# laser_zender.net
KiCad netlist of a schematic drawn in EAGLE
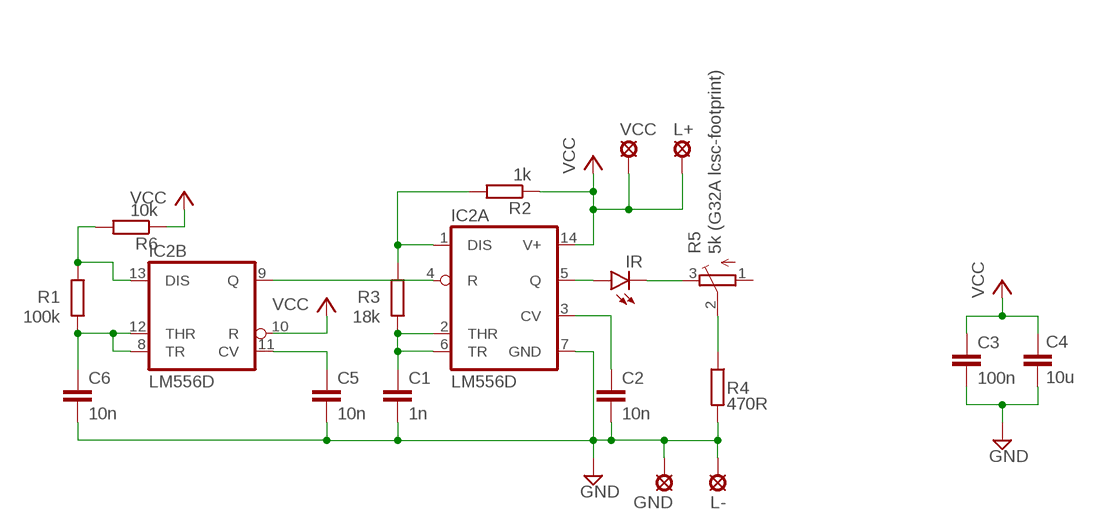
[diagram p0: schematic, sheet 1]

(export (version "E")
  (design (tool "Eeschema 10.0.6"))
  (components
    (comp (ref "C1")
      (value "1n")
      (footprint "eagle-import:C0805")
      (libsource (lib "eagle-import") (part "C-EUC0805"))
    )
    (comp (ref "C2")
      (value "10n")
      (footprint "eagle-import:C0805")
      (libsource (lib "eagle-import") (part "C-EUC0805"))
    )
    (comp (ref "C3")
      (value "100n")
      (footprint "eagle-import:C0805")
      (libsource (lib "eagle-import") (part "C-EUC0805"))
    )
    (comp (ref "C4")
      (value "10u")
      (footprint "eagle-import:C0805")
      (libsource (lib "eagle-import") (part "C-EUC0805"))
    )
    (comp (ref "C5")
      (value "10n")
      (footprint "eagle-import:C0805")
      (libsource (lib "eagle-import") (part "C-EUC0805"))
    )
    (comp (ref "C6")
      (value "10n")
      (footprint "eagle-import:C0805")
      (libsource (lib "eagle-import") (part "C-EUC0805"))
    )
    (comp (ref "GND")
      (value "LSP10")
      (footprint "eagle-import:LSP10")
      (libsource (lib "eagle-import") (part "LSP10"))
    )
    (comp (ref "IC2")
      (value "LM556D")
      (footprint "eagle-import:SO14")
      (libsource (lib "eagle-import") (part "556DLM"))
    )
    (comp (ref "IR")
      (value "LEDCHIPLED_0805")
      (footprint "eagle-import:CHIPLED_0805")
      (libsource (lib "eagle-import") (part "LEDCHIPLED_0805"))
    )
    (comp (ref "L+")
      (value "LSP10")
      (footprint "eagle-import:LSP10")
      (libsource (lib "eagle-import") (part "LSP10"))
    )
    (comp (ref "L-")
      (value "LSP10")
      (footprint "eagle-import:LSP10")
      (libsource (lib "eagle-import") (part "LSP10"))
    )
    (comp (ref "R1")
      (value "100k")
      (footprint "eagle-import:R0805")
      (libsource (lib "eagle-import") (part "R-EU_R0805"))
    )
    (comp (ref "R2")
      (value "1k")
      (footprint "eagle-import:R0805")
      (libsource (lib "eagle-import") (part "R-EU_R0805"))
    )
    (comp (ref "R3")
      (value "18k")
      (footprint "eagle-import:R0805")
      (libsource (lib "eagle-import") (part "R-EU_R0805"))
    )
    (comp (ref "R4")
      (value "470R")
      (footprint "eagle-import:R0805")
      (libsource (lib "eagle-import") (part "R-EU_R0805"))
    )
    (comp (ref "R5")
      (value "5k (G32A lcsc-footprint)")
      (footprint "eagle-import:3223W")
      (libsource (lib "eagle-import") (part "TRIM_EU-3223W"))
    )
    (comp (ref "R6")
      (value "10k")
      (footprint "eagle-import:R0805")
      (libsource (lib "eagle-import") (part "R-EU_R0805"))
    )
    (comp (ref "VCC")
      (value "LSP10")
      (footprint "eagle-import:LSP10")
      (libsource (lib "eagle-import") (part "LSP10"))
    )
  )
  (nets
    (net (code "1") (name "GND") (class "Default")
      (node (ref "C1") (pin "2") (pinfunction "2_2") (pintype "passive"))
      (node (ref "C2") (pin "2") (pinfunction "2_2") (pintype "passive"))
      (node (ref "C3") (pin "2") (pinfunction "2_2") (pintype "passive"))
      (node (ref "C4") (pin "2") (pinfunction "2_2") (pintype "passive"))
      (node (ref "C5") (pin "2") (pinfunction "2_2") (pintype "passive"))
      (node (ref "C6") (pin "2") (pinfunction "2_2") (pintype "passive"))
      (node (ref "GND") (pin "MP") (pinfunction "MP_MP") (pintype "passive"))
      (node (ref "IC2") (pin "7") (pinfunction "GND_7") (pintype "power_in"))
      (node (ref "L-") (pin "MP") (pinfunction "MP_MP") (pintype "passive"))
      (node (ref "R4") (pin "2") (pinfunction "2_2") (pintype "passive"))
    )
    (net (code "2") (name "Net-(IC2A-CV)") (class "Default")
      (node (ref "C2") (pin "1") (pinfunction "1_1") (pintype "passive"))
      (node (ref "IC2") (pin "3") (pinfunction "CV_3") (pintype "input"))
    )
    (net (code "3") (name "Net-(IC2A-DIS)") (class "Default")
      (node (ref "IC2") (pin "1") (pinfunction "DIS_1") (pintype "input"))
      (node (ref "R2") (pin "2") (pinfunction "2_2") (pintype "passive"))
      (node (ref "R3") (pin "2") (pinfunction "2_2") (pintype "passive"))
    )
    (net (code "4") (name "Net-(IC2A-Q)") (class "Default")
      (node (ref "IC2") (pin "5") (pinfunction "Q_5") (pintype "output"))
      (node (ref "IR") (pin "A") (pinfunction "A_A") (pintype "passive"))
    )
    (net (code "5") (name "Net-(IC2A-R)") (class "Default")
      (node (ref "IC2") (pin "4") (pinfunction "R_4") (pintype "input"))
      (node (ref "IC2") (pin "9") (pinfunction "Q_9") (pintype "output"))
    )
    (net (code "6") (name "Net-(IC2A-THR)") (class "Default")
      (node (ref "C1") (pin "1") (pinfunction "1_1") (pintype "passive"))
      (node (ref "IC2") (pin "2") (pinfunction "THR_2") (pintype "input"))
      (node (ref "IC2") (pin "6") (pinfunction "TR_6") (pintype "input"))
      (node (ref "R3") (pin "1") (pinfunction "1_1") (pintype "passive"))
    )
    (net (code "7") (name "Net-(IC2B-CV)") (class "Default")
      (node (ref "C5") (pin "1") (pinfunction "1_1") (pintype "passive"))
      (node (ref "IC2") (pin "11") (pinfunction "CV_11") (pintype "input"))
    )
    (net (code "8") (name "Net-(IC2B-DIS)") (class "Default")
      (node (ref "IC2") (pin "13") (pinfunction "DIS_13") (pintype "input"))
      (node (ref "R1") (pin "2") (pinfunction "2_2") (pintype "passive"))
      (node (ref "R6") (pin "2") (pinfunction "2_2") (pintype "passive"))
    )
    (net (code "9") (name "Net-(IC2B-THR)") (class "Default")
      (node (ref "C6") (pin "1") (pinfunction "1_1") (pintype "passive"))
      (node (ref "IC2") (pin "12") (pinfunction "THR_12") (pintype "input"))
      (node (ref "IC2") (pin "8") (pinfunction "TR_8") (pintype "input"))
      (node (ref "R1") (pin "1") (pinfunction "1_1") (pintype "passive"))
    )
    (net (code "10") (name "Net-(R5-E)") (class "Default")
      (node (ref "IR") (pin "C") (pinfunction "C_C") (pintype "passive"))
      (node (ref "R5") (pin "3") (pinfunction "E_3") (pintype "passive"))
    )
    (net (code "11") (name "Net-(R5-S)") (class "Default")
      (node (ref "R4") (pin "1") (pinfunction "1_1") (pintype "passive"))
      (node (ref "R5") (pin "2") (pinfunction "S_2") (pintype "passive"))
    )
    (net (code "12") (name "VCC") (class "Default")
      (node (ref "C3") (pin "1") (pinfunction "1_1") (pintype "passive"))
      (node (ref "C4") (pin "1") (pinfunction "1_1") (pintype "passive"))
      (node (ref "IC2") (pin "10") (pinfunction "R_10") (pintype "input"))
      (node (ref "IC2") (pin "14") (pinfunction "V+_14") (pintype "power_in"))
      (node (ref "L+") (pin "MP") (pinfunction "MP_MP") (pintype "passive"))
      (node (ref "R2") (pin "1") (pinfunction "1_1") (pintype "passive"))
      (node (ref "R6") (pin "1") (pinfunction "1_1") (pintype "passive"))
      (node (ref "VCC") (pin "MP") (pinfunction "MP_MP") (pintype "passive"))
    )
    (net (code "13") (name "unconnected-(R5-A-Pad1)") (class "Default")
      (node (ref "R5") (pin "1") (pinfunction "A_1") (pintype "passive"))
    )
  )
)
